# 5V_3_3V_LDO_SUPPLY.net
KiCad netlist of a schematic drawn in Altium Designer
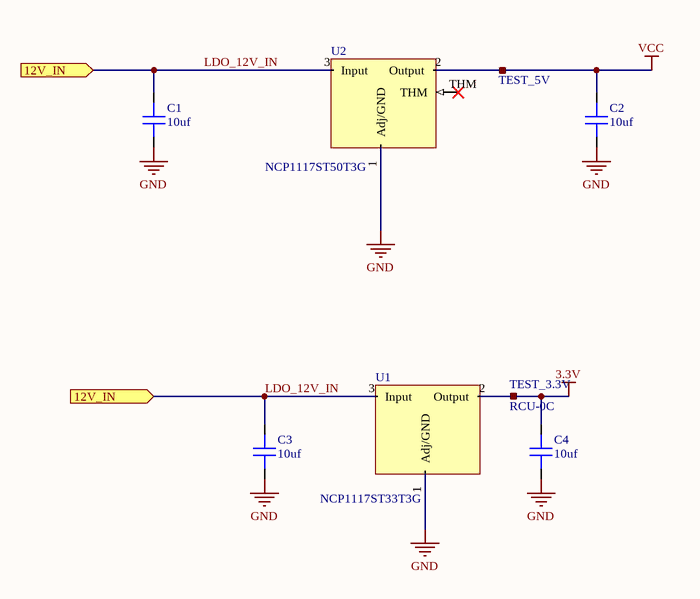
[diagram p0: 5V_3.3V_LDO_SUPPLY.SchDoc]

(export (version "E")
  (design (tool "Eeschema 10.0.6"))
  (components
    (comp (ref "C1")
      (value "10uf")
      (footprint "CAP 0603/1608")
      (fields
        (field (name "Comment") "Capacitor MLCC 10uf 16V CAP 0603/1608")
        (field (name "CREATED_BY") "Nick Mah")
      )
      (libsource (lib "Altium-Lib") (part "Capacitor"))
    )
    (comp (ref "C2")
      (value "10uf")
      (footprint "CAP 0603/1608")
      (fields
        (field (name "Comment") "Capacitor MLCC 10uf 16V CAP 0603/1608")
        (field (name "CREATED_BY") "Nick Mah")
      )
      (libsource (lib "Altium-Lib") (part "Capacitor"))
    )
    (comp (ref "C3")
      (value "10uf")
      (footprint "CAP 0603/1608")
      (fields
        (field (name "Comment") "Capacitor MLCC 10uf 16V CAP 0603/1608")
        (field (name "CREATED_BY") "Nick Mah")
      )
      (libsource (lib "Altium-Lib") (part "Capacitor"))
    )
    (comp (ref "C4")
      (value "10uf")
      (footprint "CAP 0603/1608")
      (fields
        (field (name "Comment") "Capacitor MLCC 10uf 16V CAP 0603/1608")
        (field (name "CREATED_BY") "Nick Mah")
      )
      (libsource (lib "Altium-Lib") (part "Capacitor"))
    )
    (comp (ref "TEST_3.3V")
      (value "RCU-0C")
      (footprint "RCU-0C")
      (libsource (lib "Altium-Lib") (part "RCU-0C"))
    )
    (comp (ref "TEST_5V")
      (value "RCU-0C")
      (footprint "RCU-0C")
      (libsource (lib "Altium-Lib") (part "RCU-0C"))
    )
    (comp (ref "U1")
      (value "NCP1117ST33T3G")
      (footprint "SOT-223-3")
      (description "1.0 A Low Dropout Positive and Adjustable Voltage Regulator")
      (libsource (lib "Altium-Lib") (part "NCP1117ST33T3G"))
    )
    (comp (ref "U2")
      (value "NCP1117ST50T3G")
      (footprint "SOT-223-3")
      (description "Linear Voltage Regulator IC Positive Fixed 1 Output 5V 1A SOT-223")
      (fields (field (name "CREATED_BY") "Angel Delgado"))
      (libsource (lib "Altium-Lib") (part "NCP1117ST50T3G"))
    )
  )
  (nets
    (net (code "1") (name "/LDO_12V_IN") (class "Default")
      (node (ref "C1") (pin "2") (pinfunction "2_2") (pintype "passive"))
      (node (ref "C3") (pin "2") (pinfunction "2_2") (pintype "passive"))
      (node (ref "U1") (pin "3") (pinfunction "Input_3") (pintype "input"))
      (node (ref "U2") (pin "3") (pinfunction "Input_3") (pintype "input"))
    )
    (net (code "2") (name "3.3V") (class "Default")
      (node (ref "C4") (pin "2") (pinfunction "2_2") (pintype "passive"))
      (node (ref "TEST_3.3V") (pin "1") (pintype "passive"))
      (node (ref "U1") (pin "2") (pinfunction "Output_2") (pintype "input"))
    )
    (net (code "3") (name "GND") (class "Default")
      (node (ref "C1") (pin "1") (pinfunction "1_1") (pintype "passive"))
      (node (ref "C2") (pin "1") (pinfunction "1_1") (pintype "passive"))
      (node (ref "C3") (pin "1") (pinfunction "1_1") (pintype "passive"))
      (node (ref "C4") (pin "1") (pinfunction "1_1") (pintype "passive"))
      (node (ref "U1") (pin "1") (pinfunction "Adj/GND_1") (pintype "input"))
      (node (ref "U2") (pin "1") (pinfunction "Adj/GND_1") (pintype "input"))
    )
    (net (code "4") (name "VCC") (class "Default")
      (node (ref "C2") (pin "2") (pinfunction "2_2") (pintype "passive"))
      (node (ref "TEST_5V") (pin "1") (pintype "passive"))
      (node (ref "U2") (pin "2") (pinfunction "Output_2") (pintype "input"))
    )
    (net (code "5") (name "unconnected-(U2-PadTHM)") (class "Default")
      (node (ref "U2") (pin "THM") (pinfunction "THM_THM") (pintype "input+no_connect"))
    )
  )
)
